# tlc5971-v3.net
KiCad netlist of a schematic drawn in EAGLE
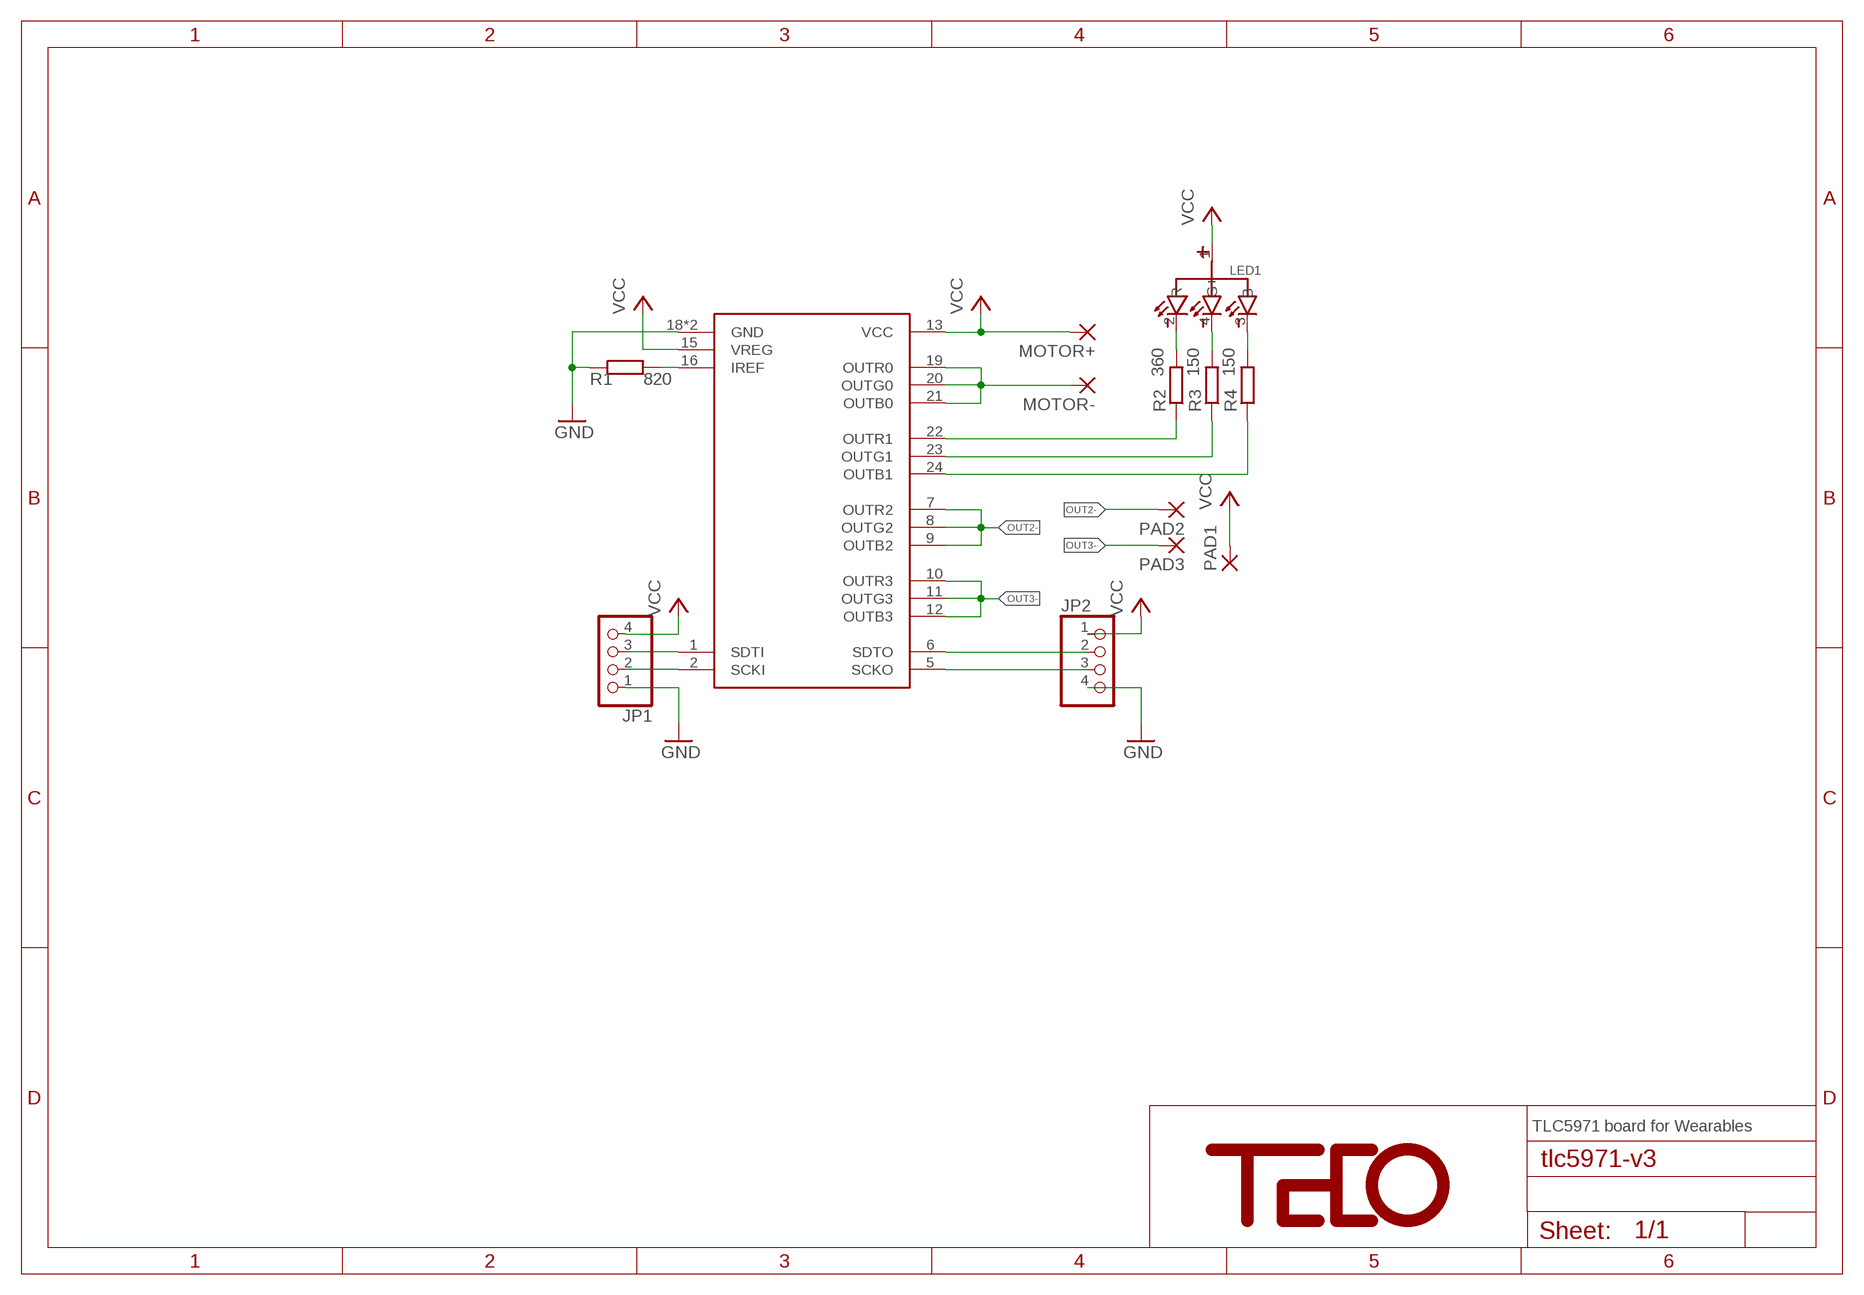
[diagram p0: schematic, sheet 1]

(export (version "E")
  (design (tool "Eeschema 10.0.6"))
  (components
    (comp (ref "JP1")
      (value "PINHD-1X4")
      (footprint "eagle-import:1X04")
      (libsource (lib "eagle-import") (part "PINHD-1X4"))
    )
    (comp (ref "JP2")
      (value "PINHD-1X4")
      (footprint "eagle-import:1X04")
      (libsource (lib "eagle-import") (part "PINHD-1X4"))
    )
    (comp (ref "LED1")
      (value "SML-LX0404SIUPGUSB")
      (footprint "eagle-import:SML_LED")
      (libsource (lib "eagle-import") (part "SML-LX0404SIUPGUSB"))
    )
    (comp (ref "MOTOR+")
      (value "SMD2")
      (footprint "eagle-import:SMD1,27-2,54")
      (libsource (lib "eagle-import") (part "SMD2"))
    )
    (comp (ref "MOTOR-")
      (value "SMD2")
      (footprint "eagle-import:SMD1,27-2,54")
      (libsource (lib "eagle-import") (part "SMD2"))
    )
    (comp (ref "PAD1")
      (value "SMD2")
      (footprint "eagle-import:SMD1,27-2,54")
      (libsource (lib "eagle-import") (part "SMD2"))
    )
    (comp (ref "PAD2")
      (value "SMD2")
      (footprint "eagle-import:SMD1,27-2,54")
      (libsource (lib "eagle-import") (part "SMD2"))
    )
    (comp (ref "PAD3")
      (value "SMD2")
      (footprint "eagle-import:SMD1,27-2,54")
      (libsource (lib "eagle-import") (part "SMD2"))
    )
    (comp (ref "R1")
      (value "820")
      (footprint "eagle-import:R0402")
      (libsource (lib "eagle-import") (part "R-EU_R0402"))
    )
    (comp (ref "R2")
      (value "360")
      (footprint "eagle-import:R0402")
      (libsource (lib "eagle-import") (part "R-EU_R0402"))
    )
    (comp (ref "R3")
      (value "150")
      (footprint "eagle-import:R0402")
      (libsource (lib "eagle-import") (part "R-EU_R0402"))
    )
    (comp (ref "R4")
      (value "150")
      (footprint "eagle-import:R0402")
      (libsource (lib "eagle-import") (part "R-EU_R0402"))
    )
    (comp (ref "U$1")
      (value "TLC5971")
      (footprint "eagle-import:RGE.24")
      (libsource (lib "eagle-import") (part "TLC5971"))
    )
    (comp (ref "U$3")
      (value "TECO-LOGO-BIG")
      (footprint "eagle-import:TECO-LOGO-BIG")
      (libsource (lib "eagle-import") (part "TECO-LOGO-BIG"))
    )
  )
  (nets
    (net (code "1") (name "GND") (class "Default")
      (node (ref "JP1") (pin "1") (pinfunction "1_1") (pintype "passive"))
      (node (ref "JP2") (pin "4") (pinfunction "4_4") (pintype "passive"))
      (node (ref "R1") (pin "1") (pinfunction "1_1") (pintype "passive"))
      (node (ref "U$1") (pin "18") (pinfunction "GND_18") (pintype "passive"))
      (node (ref "U$1") (pin "PAD") (pinfunction "GND_PAD") (pintype "passive"))
    )
    (net (code "2") (name "Net-(LED1-B)") (class "Default")
      (node (ref "LED1") (pin "3") (pinfunction "B_3") (pintype "bidirectional"))
      (node (ref "R4") (pin "2") (pinfunction "2_2") (pintype "passive"))
    )
    (net (code "3") (name "Net-(LED1-G)") (class "Default")
      (node (ref "LED1") (pin "4") (pinfunction "G_4") (pintype "bidirectional"))
      (node (ref "R3") (pin "2") (pinfunction "2_2") (pintype "passive"))
    )
    (net (code "4") (name "Net-(LED1-R)") (class "Default")
      (node (ref "LED1") (pin "2") (pinfunction "R_2") (pintype "bidirectional"))
      (node (ref "R2") (pin "2") (pinfunction "2_2") (pintype "passive"))
    )
    (net (code "5") (name "Net-(MOTOR--P)") (class "Default")
      (node (ref "MOTOR-") (pin "1") (pinfunction "P_1") (pintype "passive"))
      (node (ref "U$1") (pin "19") (pinfunction "OUTR0_19") (pintype "bidirectional"))
      (node (ref "U$1") (pin "20") (pinfunction "OUTG0_20") (pintype "bidirectional"))
      (node (ref "U$1") (pin "21") (pinfunction "OUTB0_21") (pintype "bidirectional"))
    )
    (net (code "6") (name "Net-(U$1-IREF)") (class "Default")
      (node (ref "R1") (pin "2") (pinfunction "2_2") (pintype "passive"))
      (node (ref "U$1") (pin "16") (pinfunction "IREF_16") (pintype "bidirectional"))
    )
    (net (code "7") (name "Net-(U$1-OUTB1)") (class "Default")
      (node (ref "R4") (pin "1") (pinfunction "1_1") (pintype "passive"))
      (node (ref "U$1") (pin "24") (pinfunction "OUTB1_24") (pintype "bidirectional"))
    )
    (net (code "8") (name "Net-(U$1-OUTG1)") (class "Default")
      (node (ref "R3") (pin "1") (pinfunction "1_1") (pintype "passive"))
      (node (ref "U$1") (pin "23") (pinfunction "OUTG1_23") (pintype "bidirectional"))
    )
    (net (code "9") (name "Net-(U$1-OUTR1)") (class "Default")
      (node (ref "R2") (pin "1") (pinfunction "1_1") (pintype "passive"))
      (node (ref "U$1") (pin "22") (pinfunction "OUTR1_22") (pintype "bidirectional"))
    )
    (net (code "10") (name "Net-(U$1-SCKI)") (class "Default")
      (node (ref "JP1") (pin "2") (pinfunction "2_2") (pintype "passive"))
      (node (ref "U$1") (pin "2") (pinfunction "SCKI_2") (pintype "bidirectional"))
    )
    (net (code "11") (name "Net-(U$1-SCKO)") (class "Default")
      (node (ref "JP2") (pin "3") (pinfunction "3_3") (pintype "passive"))
      (node (ref "U$1") (pin "5") (pinfunction "SCKO_5") (pintype "bidirectional"))
    )
    (net (code "12") (name "Net-(U$1-SDTI)") (class "Default")
      (node (ref "JP1") (pin "3") (pinfunction "3_3") (pintype "passive"))
      (node (ref "U$1") (pin "1") (pinfunction "SDTI_1") (pintype "bidirectional"))
    )
    (net (code "13") (name "Net-(U$1-SDTO)") (class "Default")
      (node (ref "JP2") (pin "2") (pinfunction "2_2") (pintype "passive"))
      (node (ref "U$1") (pin "6") (pinfunction "SDTO_6") (pintype "bidirectional"))
    )
    (net (code "14") (name "OUT2-") (class "Default")
      (node (ref "PAD2") (pin "1") (pinfunction "P_1") (pintype "passive"))
      (node (ref "U$1") (pin "7") (pinfunction "OUTR2_7") (pintype "bidirectional"))
      (node (ref "U$1") (pin "8") (pinfunction "OUTG2_8") (pintype "bidirectional"))
      (node (ref "U$1") (pin "9") (pinfunction "OUTB2_9") (pintype "bidirectional"))
    )
    (net (code "15") (name "OUT3-") (class "Default")
      (node (ref "PAD3") (pin "1") (pinfunction "P_1") (pintype "passive"))
      (node (ref "U$1") (pin "10") (pinfunction "OUTR3_10") (pintype "bidirectional"))
      (node (ref "U$1") (pin "11") (pinfunction "OUTG3_11") (pintype "bidirectional"))
      (node (ref "U$1") (pin "12") (pinfunction "OUTB3_12") (pintype "bidirectional"))
    )
    (net (code "16") (name "VCC") (class "Default")
      (node (ref "JP1") (pin "4") (pinfunction "4_4") (pintype "passive"))
      (node (ref "JP2") (pin "1") (pinfunction "1_1") (pintype "passive"))
      (node (ref "LED1") (pin "1") (pinfunction "+_1") (pintype "bidirectional"))
      (node (ref "MOTOR+") (pin "1") (pinfunction "P_1") (pintype "passive"))
      (node (ref "PAD1") (pin "1") (pinfunction "P_1") (pintype "passive"))
      (node (ref "U$1") (pin "13") (pinfunction "VCC_13") (pintype "bidirectional"))
      (node (ref "U$1") (pin "15") (pinfunction "VREG_15") (pintype "bidirectional"))
    )
  )
)
